# RTMS_Voltage_Regulation_Circuit.net
KiCad netlist of a schematic drawn in EAGLE
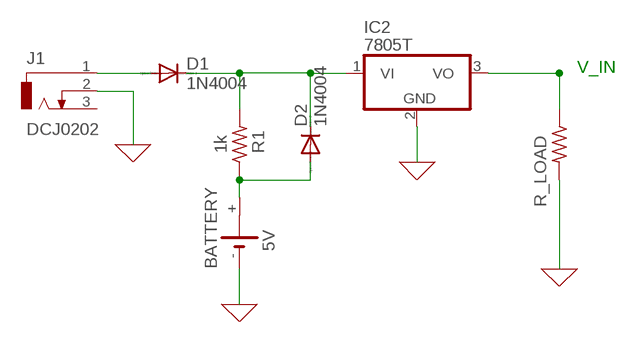
[diagram p0: schematic, sheet 1]

(export (version "E")
  (design (tool "Eeschema 10.0.6"))
  (components
    (comp (ref "BATTERY")
      (value "5V")
      (footprint "eagle-import:CRAA")
      (libsource (lib "eagle-import") (part "CR-AA"))
    )
    (comp (ref "D1")
      (value "1N4004")
      (footprint "eagle-import:DO41-10")
      (libsource (lib "eagle-import") (part "1N4004"))
    )
    (comp (ref "D2")
      (value "1N4004")
      (footprint "eagle-import:DO41-10")
      (libsource (lib "eagle-import") (part "1N4004"))
    )
    (comp (ref "IC2")
      (value "7805T")
      (footprint "eagle-import:TO220H")
      (libsource (lib "eagle-import") (part "78T05"))
    )
    (comp (ref "J1")
      (value "DCJ0202")
      (footprint "eagle-import:DCJ0202")
      (libsource (lib "eagle-import") (part "DCJ0202"))
    )
    (comp (ref "R1")
      (value "1k")
      (footprint "eagle-import:0207_10")
      (fields (field (name "SPICEPREFIX") "1000 Ohm"))
      (libsource (lib "eagle-import") (part "R-US_0207/10"))
    )
    (comp (ref "R_LOAD")
      (value "R-US_0207/10")
      (footprint "eagle-import:0207_10")
      (fields (field (name "SPICEPREFIX") "R_Load"))
      (libsource (lib "eagle-import") (part "R-US_0207/10"))
    )
  )
  (nets
    (net (code "1") (name "GND") (class "Default")
      (node (ref "BATTERY") (pin "-") (pinfunction "-_-") (pintype "passive"))
      (node (ref "IC2") (pin "2") (pinfunction "GND_2") (pintype "passive"))
      (node (ref "J1") (pin "2") (pinfunction "2_2") (pintype "passive"))
      (node (ref "R_LOAD") (pin "2") (pinfunction "2_2") (pintype "passive"))
    )
    (net (code "2") (name "Net-(BATTERY-Pad+)") (class "Default")
      (node (ref "BATTERY") (pin "+") (pinfunction "+_+") (pintype "passive"))
      (node (ref "D2") (pin "A") (pinfunction "A_A") (pintype "passive"))
      (node (ref "R1") (pin "1") (pinfunction "1_1") (pintype "passive"))
    )
    (net (code "3") (name "Net-(D1-PadA)") (class "Default")
      (node (ref "D1") (pin "A") (pinfunction "A_A") (pintype "passive"))
      (node (ref "J1") (pin "1") (pinfunction "1_1") (pintype "passive"))
    )
    (net (code "4") (name "Net-(IC2-VI)") (class "Default")
      (node (ref "D1") (pin "C") (pinfunction "C_C") (pintype "passive"))
      (node (ref "D2") (pin "C") (pinfunction "C_C") (pintype "passive"))
      (node (ref "IC2") (pin "1") (pinfunction "VI_1") (pintype "input"))
      (node (ref "R1") (pin "2") (pinfunction "2_2") (pintype "passive"))
    )
    (net (code "5") (name "Net-(IC2-VO)") (class "Default")
      (node (ref "IC2") (pin "3") (pinfunction "VO_3") (pintype "passive"))
      (node (ref "R_LOAD") (pin "1") (pinfunction "1_1") (pintype "passive"))
    )
    (net (code "6") (name "unconnected-(BATTERY-+-Pad+@1)") (class "Default")
      (node (ref "BATTERY") (pin "+@1") (pinfunction "+_+@1") (pintype "passive"))
    )
    (net (code "7") (name "unconnected-(J1-Pad3)") (class "Default")
      (node (ref "J1") (pin "3") (pinfunction "3_3") (pintype "passive"))
    )
  )
)
